# Bokskort_top.net
KiCad netlist of a schematic drawn in Altium Designer
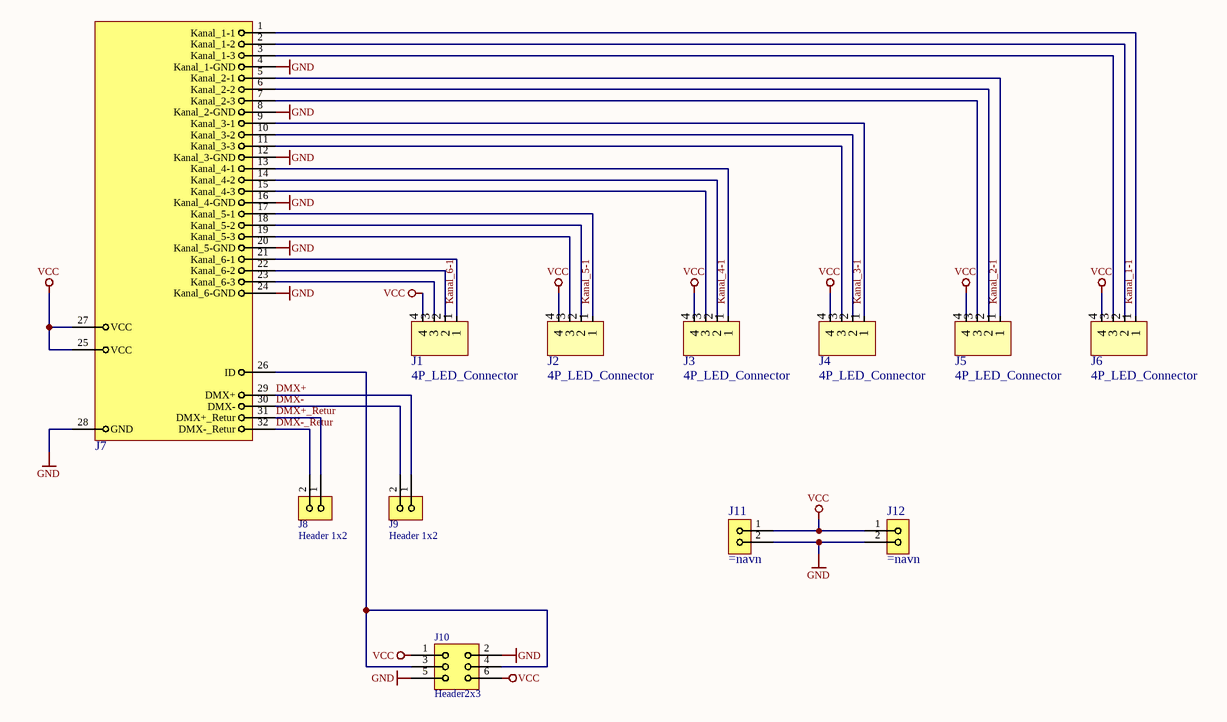
[diagram p0: Bokskort_top.SchDoc]

(export (version "E")
  (design (tool "Eeschema 10.0.6"))
  (components
    (comp (ref "J1")
      (value "4P_LED_Connector")
      (footprint "LED_solder_connections")
      (libsource (lib "4P_LED_connector") (part "4P_LED_Connector"))
    )
    (comp (ref "J2")
      (value "4P_LED_Connector")
      (footprint "LED_solder_connections")
      (libsource (lib "4P_LED_connector") (part "4P_LED_Connector"))
    )
    (comp (ref "J3")
      (value "4P_LED_Connector")
      (footprint "LED_solder_connections")
      (libsource (lib "4P_LED_connector") (part "4P_LED_Connector"))
    )
    (comp (ref "J4")
      (value "4P_LED_Connector")
      (footprint "LED_solder_connections")
      (libsource (lib "4P_LED_connector") (part "4P_LED_Connector"))
    )
    (comp (ref "J5")
      (value "4P_LED_Connector")
      (footprint "LED_solder_connections")
      (libsource (lib "4P_LED_connector") (part "4P_LED_Connector"))
    )
    (comp (ref "J6")
      (value "4P_LED_Connector")
      (footprint "LED_solder_connections")
      (libsource (lib "4P_LED_connector") (part "4P_LED_Connector"))
    )
    (comp (ref "J7")
      (value "Lysreklameparalellbusskontakt2015_FEMALE")
      (footprint "HDRRAF32W64P254_2X16_4064X1260X600B")
      (libsource (lib "Lysreklameparalellbusskontakt2015_FEMALE") (part "Lysreklameparalellbusskontakt2015_FEMALE"))
    )
    (comp (ref "J8")
      (value "Header 1x2")
      (footprint "HDRV2W64P254_1X2_508X254X900B")
      (description "2,54mm pitch")
      (libsource (lib "OVLib") (part "Header1x2"))
    )
    (comp (ref "J9")
      (value "Header 1x2")
      (footprint "HDRV2W64P254_1X2_508X254X900B")
      (description "2,54mm pitch")
      (libsource (lib "OVLib") (part "Header1x2"))
    )
    (comp (ref "J10")
      (value "Header2x3")
      (footprint "HDRV6W64P254_2X3_762X508X900B")
      (description "2,54mm pitch")
      (libsource (lib "OVLib") (part "Header2x3"))
    )
    (comp (ref "J11") (value "~") (footprint "PSU_Holes_2mm") (libsource (lib "") (part "2PConnector_1")))
    (comp (ref "J12")
      (value "~")
      (footprint "PSU_Holes_2mm")
      (libsource (lib "PSU_Holes_2mm") (part "2PConnector"))
    )
  )
  (nets
    (net (code "1") (name "/DMX+") (class "Default")
      (node (ref "J7") (pin "29") (pinfunction "DMX+_29") (pintype "passive"))
      (node (ref "J9") (pin "1") (pinfunction "1_1") (pintype "passive"))
    )
    (net (code "2") (name "/DMX+_Retur") (class "Default")
      (node (ref "J7") (pin "31") (pinfunction "DMX+_Retur_31") (pintype "passive"))
      (node (ref "J8") (pin "1") (pinfunction "1_1") (pintype "passive"))
    )
    (net (code "3") (name "/DMX-") (class "Default")
      (node (ref "J7") (pin "30") (pinfunction "DMX-_30") (pintype "passive"))
      (node (ref "J9") (pin "2") (pinfunction "2_2") (pintype "passive"))
    )
    (net (code "4") (name "/DMX-_Retur") (class "Default")
      (node (ref "J7") (pin "32") (pinfunction "DMX-_Retur_32") (pintype "passive"))
      (node (ref "J8") (pin "2") (pinfunction "2_2") (pintype "passive"))
    )
    (net (code "5") (name "/Kanal_1-1") (class "Default")
      (node (ref "J6") (pin "1") (pinfunction "1_1") (pintype "passive"))
      (node (ref "J7") (pin "1") (pinfunction "Kanal_1-1_1") (pintype "passive"))
    )
    (net (code "6") (name "/Kanal_2-1") (class "Default")
      (node (ref "J5") (pin "1") (pinfunction "1_1") (pintype "passive"))
      (node (ref "J7") (pin "5") (pinfunction "Kanal_2-1_5") (pintype "passive"))
    )
    (net (code "7") (name "/Kanal_3-1") (class "Default")
      (node (ref "J4") (pin "1") (pinfunction "1_1") (pintype "passive"))
      (node (ref "J7") (pin "9") (pinfunction "Kanal_3-1_9") (pintype "passive"))
    )
    (net (code "8") (name "/Kanal_4-1") (class "Default")
      (node (ref "J3") (pin "1") (pinfunction "1_1") (pintype "passive"))
      (node (ref "J7") (pin "13") (pinfunction "Kanal_4-1_13") (pintype "passive"))
    )
    (net (code "9") (name "/Kanal_5-1") (class "Default")
      (node (ref "J2") (pin "1") (pinfunction "1_1") (pintype "passive"))
      (node (ref "J7") (pin "17") (pinfunction "Kanal_5-1_17") (pintype "passive"))
    )
    (net (code "10") (name "/Kanal_6-1") (class "Default")
      (node (ref "J1") (pin "1") (pinfunction "1_1") (pintype "passive"))
      (node (ref "J7") (pin "21") (pinfunction "Kanal_6-1_21") (pintype "passive"))
    )
    (net (code "11") (name "GND") (class "Default")
      (node (ref "J10") (pin "2") (pinfunction "2_2") (pintype "passive"))
      (node (ref "J10") (pin "5") (pinfunction "5_5") (pintype "passive"))
      (node (ref "J11") (pin "2") (pinfunction "2_2") (pintype "passive"))
      (node (ref "J12") (pin "2") (pinfunction "2_2") (pintype "passive"))
      (node (ref "J7") (pin "12") (pinfunction "Kanal_3-GND_12") (pintype "passive"))
      (node (ref "J7") (pin "16") (pinfunction "Kanal_4-GND_16") (pintype "passive"))
      (node (ref "J7") (pin "20") (pinfunction "Kanal_5-GND_20") (pintype "passive"))
      (node (ref "J7") (pin "24") (pinfunction "Kanal_6-GND_24") (pintype "passive"))
      (node (ref "J7") (pin "28") (pinfunction "GND_28") (pintype "passive"))
      (node (ref "J7") (pin "4") (pinfunction "Kanal_1-GND_4") (pintype "passive"))
      (node (ref "J7") (pin "8") (pinfunction "Kanal_2-GND_8") (pintype "passive"))
    )
    (net (code "12") (name "Net-(J7-ID)") (class "Default")
      (node (ref "J10") (pin "3") (pinfunction "3_3") (pintype "passive"))
      (node (ref "J10") (pin "4") (pinfunction "4_4") (pintype "passive"))
      (node (ref "J7") (pin "26") (pinfunction "ID_26") (pintype "passive"))
    )
    (net (code "13") (name "Net-(J7-Kanal_1-2)") (class "Default")
      (node (ref "J6") (pin "2") (pinfunction "2_2") (pintype "passive"))
      (node (ref "J7") (pin "2") (pinfunction "Kanal_1-2_2") (pintype "passive"))
    )
    (net (code "14") (name "Net-(J7-Kanal_1-3)") (class "Default")
      (node (ref "J6") (pin "3") (pinfunction "3_3") (pintype "passive"))
      (node (ref "J7") (pin "3") (pinfunction "Kanal_1-3_3") (pintype "passive"))
    )
    (net (code "15") (name "Net-(J7-Kanal_2-2)") (class "Default")
      (node (ref "J5") (pin "2") (pinfunction "2_2") (pintype "passive"))
      (node (ref "J7") (pin "6") (pinfunction "Kanal_2-2_6") (pintype "passive"))
    )
    (net (code "16") (name "Net-(J7-Kanal_2-3)") (class "Default")
      (node (ref "J5") (pin "3") (pinfunction "3_3") (pintype "passive"))
      (node (ref "J7") (pin "7") (pinfunction "Kanal_2-3_7") (pintype "passive"))
    )
    (net (code "17") (name "Net-(J7-Kanal_3-2)") (class "Default")
      (node (ref "J4") (pin "2") (pinfunction "2_2") (pintype "passive"))
      (node (ref "J7") (pin "10") (pinfunction "Kanal_3-2_10") (pintype "passive"))
    )
    (net (code "18") (name "Net-(J7-Kanal_3-3)") (class "Default")
      (node (ref "J4") (pin "3") (pinfunction "3_3") (pintype "passive"))
      (node (ref "J7") (pin "11") (pinfunction "Kanal_3-3_11") (pintype "passive"))
    )
    (net (code "19") (name "Net-(J7-Kanal_4-2)") (class "Default")
      (node (ref "J3") (pin "2") (pinfunction "2_2") (pintype "passive"))
      (node (ref "J7") (pin "14") (pinfunction "Kanal_4-2_14") (pintype "passive"))
    )
    (net (code "20") (name "Net-(J7-Kanal_4-3)") (class "Default")
      (node (ref "J3") (pin "3") (pinfunction "3_3") (pintype "passive"))
      (node (ref "J7") (pin "15") (pinfunction "Kanal_4-3_15") (pintype "passive"))
    )
    (net (code "21") (name "Net-(J7-Kanal_5-2)") (class "Default")
      (node (ref "J2") (pin "2") (pinfunction "2_2") (pintype "passive"))
      (node (ref "J7") (pin "18") (pinfunction "Kanal_5-2_18") (pintype "passive"))
    )
    (net (code "22") (name "Net-(J7-Kanal_5-3)") (class "Default")
      (node (ref "J2") (pin "3") (pinfunction "3_3") (pintype "passive"))
      (node (ref "J7") (pin "19") (pinfunction "Kanal_5-3_19") (pintype "passive"))
    )
    (net (code "23") (name "Net-(J7-Kanal_6-2)") (class "Default")
      (node (ref "J1") (pin "2") (pinfunction "2_2") (pintype "passive"))
      (node (ref "J7") (pin "22") (pinfunction "Kanal_6-2_22") (pintype "passive"))
    )
    (net (code "24") (name "Net-(J7-Kanal_6-3)") (class "Default")
      (node (ref "J1") (pin "3") (pinfunction "3_3") (pintype "passive"))
      (node (ref "J7") (pin "23") (pinfunction "Kanal_6-3_23") (pintype "passive"))
    )
    (net (code "25") (name "VCC") (class "Default")
      (node (ref "J1") (pin "4") (pinfunction "4_4") (pintype "passive"))
      (node (ref "J10") (pin "1") (pinfunction "1_1") (pintype "passive"))
      (node (ref "J10") (pin "6") (pinfunction "6_6") (pintype "passive"))
      (node (ref "J11") (pin "1") (pinfunction "1_1") (pintype "passive"))
      (node (ref "J12") (pin "1") (pinfunction "1_1") (pintype "passive"))
      (node (ref "J2") (pin "4") (pinfunction "4_4") (pintype "passive"))
      (node (ref "J3") (pin "4") (pinfunction "4_4") (pintype "passive"))
      (node (ref "J4") (pin "4") (pinfunction "4_4") (pintype "passive"))
      (node (ref "J5") (pin "4") (pinfunction "4_4") (pintype "passive"))
      (node (ref "J6") (pin "4") (pinfunction "4_4") (pintype "passive"))
      (node (ref "J7") (pin "25") (pinfunction "VCC_25") (pintype "passive"))
      (node (ref "J7") (pin "27") (pinfunction "VCC_27") (pintype "passive"))
    )
  )
)
